# BOARD_POWER.net
KiCad netlist of a schematic drawn in Altium Designer
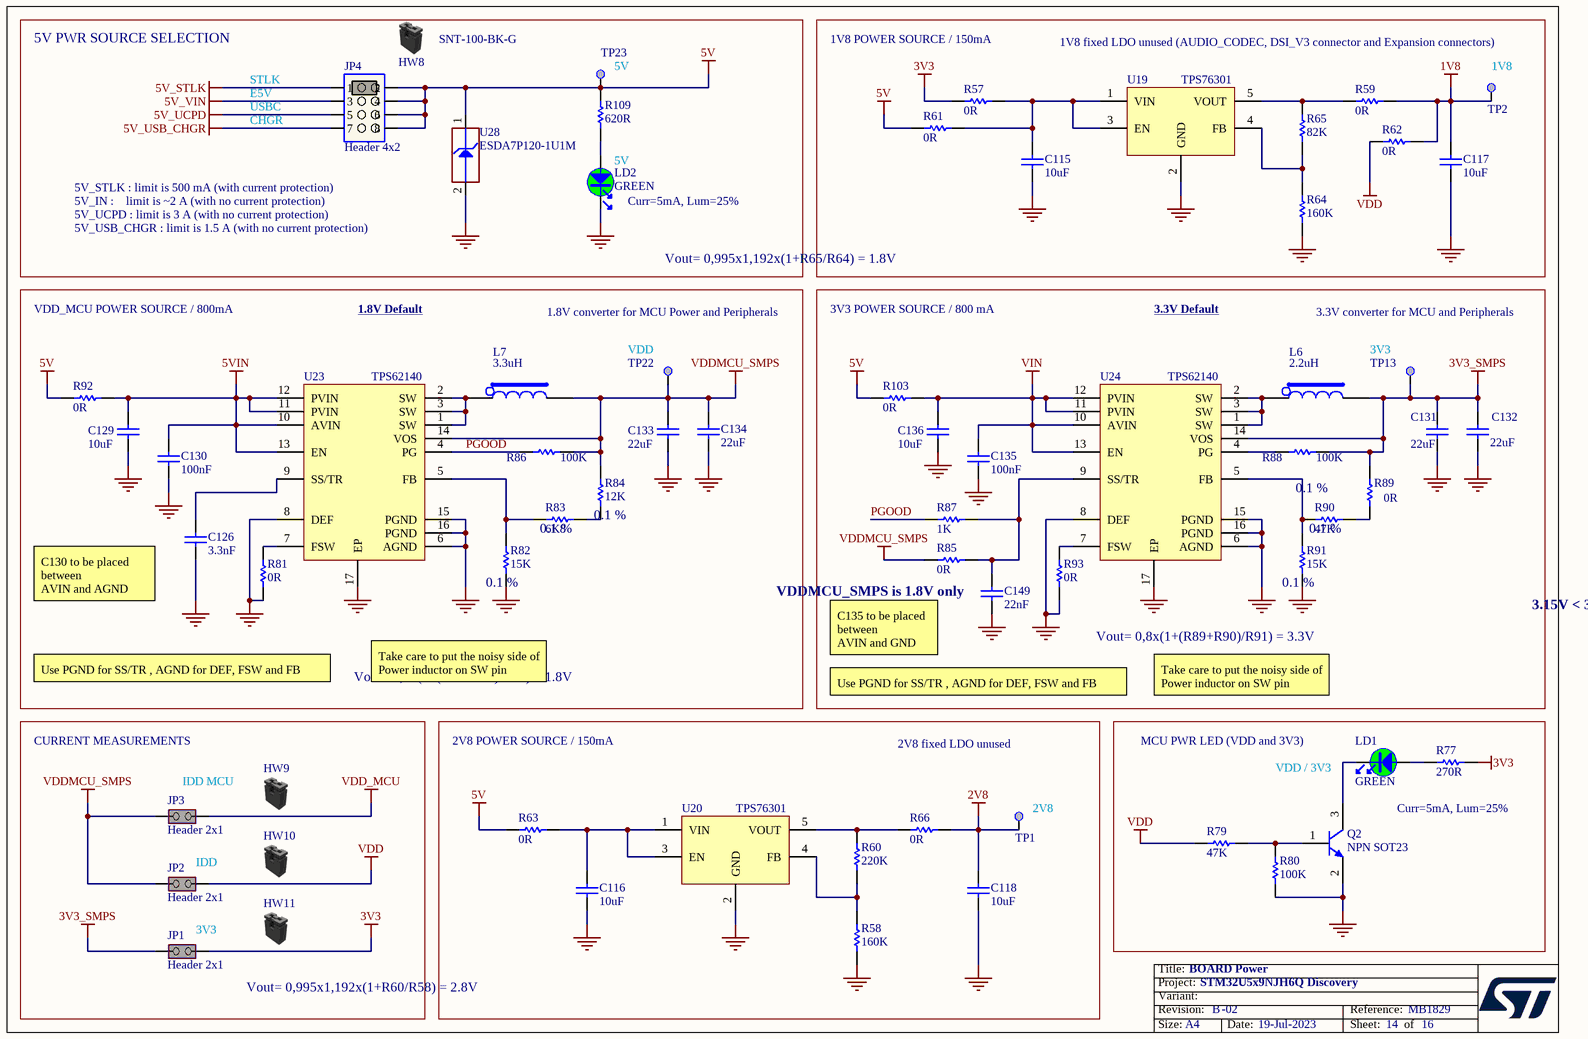
[diagram p0: BOARD_POWER.SchDoc]

(export (version "E")
  (design (tool "Eeschema 10.0.6"))
  (components
    (comp (ref "C115")
      (value "10uF")
      (footprint "MCD_PARTS:C0603_H0P8")
      (description "Capacitor, MLCC, 10uF, 10V, X5R, +/-10%, 0603, T=0.8mm")
      (fields (field (name "INTERNAL_PART_NUMBER") "MCD-02605") (field (name "MANUFACTURER") "YAGEO"))
      (libsource (lib "MCD_PARTS_database") (part "Capacitor"))
    )
    (comp (ref "C116")
      (value "10uF")
      (footprint "MCD_PARTS:C0603_H0P8")
      (description "Capacitor, MLCC, 10uF, 10V, X5R, +/-10%, 0603, T=0.8mm")
      (fields (field (name "INTERNAL_PART_NUMBER") "MCD-02605") (field (name "MANUFACTURER") "YAGEO"))
      (libsource (lib "MCD_PARTS_database") (part "Capacitor"))
    )
    (comp (ref "C117")
      (value "10uF")
      (footprint "MCD_PARTS:C0603_H0P8")
      (description "Capacitor, MLCC, 10uF, 10V, X5R, +/-10%, 0603, T=0.8mm")
      (fields (field (name "INTERNAL_PART_NUMBER") "MCD-02605") (field (name "MANUFACTURER") "YAGEO"))
      (libsource (lib "MCD_PARTS_database") (part "Capacitor"))
    )
    (comp (ref "C118")
      (value "10uF")
      (footprint "MCD_PARTS:C0603_H0P8")
      (description "Capacitor, MLCC, 10uF, 10V, X5R, +/-10%, 0603, T=0.8mm")
      (fields (field (name "INTERNAL_PART_NUMBER") "MCD-02605") (field (name "MANUFACTURER") "YAGEO"))
      (libsource (lib "MCD_PARTS_database") (part "Capacitor"))
    )
    (comp (ref "C126")
      (value "3.3nF")
      (footprint "MCD_PARTS:C0402")
      (description "Capacitor, MLCC, 3.3nF, 50V, X7R, +/-10%, 0402, T=0.5mm")
      (fields (field (name "INTERNAL_PART_NUMBER") "MCD-02628") (field (name "MANUFACTURER") "YAGEO"))
      (libsource (lib "MCD_PARTS_database") (part "Capacitor"))
    )
    (comp (ref "C129")
      (value "10uF")
      (footprint "MCD_PARTS:C1206_H1P6")
      (description "Capacitor, MLCC, 10uF, 25V, X5R, +/-10%, 1206, T=1.6mm")
      (fields (field (name "INTERNAL_PART_NUMBER") "MCD-02610") (field (name "MANUFACTURER") "YAGEO"))
      (libsource (lib "MCD_PARTS_database") (part "Capacitor"))
    )
    (comp (ref "C130")
      (value "100nF")
      (footprint "MCD_PARTS:C0402")
      (description "Capacitor, MLCC, 100nF, 16V, X7R, +/-10%, 0402, T=0.5mm")
      (fields (field (name "INTERNAL_PART_NUMBER") "MCD-00006") (field (name "MANUFACTURER") "YAGEO"))
      (libsource (lib "MCD_PARTS_database") (part "Capacitor"))
    )
    (comp (ref "C131")
      (value "22uF")
      (footprint "MCD_PARTS:C0603_H0P8")
      (description "Capacitor, MLCC, 22uF, 10V, X5R, +/-20%, 0603, T=0.8mm")
      (fields (field (name "INTERNAL_PART_NUMBER") "MCD-02607") (field (name "MANUFACTURER") "YAGEO"))
      (libsource (lib "MCD_PARTS_database") (part "Capacitor"))
    )
    (comp (ref "C132")
      (value "22uF")
      (footprint "MCD_PARTS:C0603_H0P8")
      (description "Capacitor, MLCC, 22uF, 10V, X5R, +/-20%, 0603, T=0.8mm")
      (fields (field (name "INTERNAL_PART_NUMBER") "MCD-02607") (field (name "MANUFACTURER") "YAGEO"))
      (libsource (lib "MCD_PARTS_database") (part "Capacitor"))
    )
    (comp (ref "C133")
      (value "22uF")
      (footprint "MCD_PARTS:C0603_H0P8")
      (description "Capacitor, MLCC, 22uF, 10V, X5R, +/-20%, 0603, T=0.8mm")
      (fields (field (name "INTERNAL_PART_NUMBER") "MCD-02607") (field (name "MANUFACTURER") "YAGEO"))
      (libsource (lib "MCD_PARTS_database") (part "Capacitor"))
    )
    (comp (ref "C134")
      (value "22uF")
      (footprint "MCD_PARTS:C0603_H0P8")
      (description "Capacitor, MLCC, 22uF, 10V, X5R, +/-20%, 0603, T=0.8mm")
      (fields (field (name "INTERNAL_PART_NUMBER") "MCD-02607") (field (name "MANUFACTURER") "YAGEO"))
      (libsource (lib "MCD_PARTS_database") (part "Capacitor"))
    )
    (comp (ref "C135")
      (value "100nF")
      (footprint "MCD_PARTS:C0402")
      (description "Capacitor, MLCC, 100nF, 16V, X7R, +/-10%, 0402, T=0.5mm")
      (fields (field (name "INTERNAL_PART_NUMBER") "MCD-00006") (field (name "MANUFACTURER") "YAGEO"))
      (libsource (lib "MCD_PARTS_database") (part "Capacitor"))
    )
    (comp (ref "C136")
      (value "10uF")
      (footprint "MCD_PARTS:C1206_H1P6")
      (description "Capacitor, MLCC, 10uF, 25V, X5R, +/-10%, 1206, T=1.6mm")
      (fields (field (name "INTERNAL_PART_NUMBER") "MCD-02610") (field (name "MANUFACTURER") "YAGEO"))
      (libsource (lib "MCD_PARTS_database") (part "Capacitor"))
    )
    (comp (ref "C149")
      (value "22nF")
      (footprint "MCD_PARTS:C0402")
      (description "Capacitor, MLCC, 22nF, 50V, X7R, +/-10%, 0402, T=0.5mm")
      (fields (field (name "INTERNAL_PART_NUMBER") "MCD-03051") (field (name "MANUFACTURER") "YAGEO"))
      (libsource (lib "MCD_PARTS_database") (part "Capacitor"))
    )
    (comp (ref "HW8")
      (value "SNT-100-BK-G")
      (description "SHUNT 2.54mm BLACK")
      (fields (field (name "INTERNAL_PART_NUMBER") "MCD-00043") (field (name "MANUFACTURER") "SAMTEC"))
      (libsource (lib "MCD_PARTS_database") (part "Shunt Black 2.54mm"))
    )
    (comp (ref "HW9")
      (value "Shunt Black 2.54mm")
      (description "SHUNT 2.54mm BLACK")
      (fields (field (name "INTERNAL_PART_NUMBER") "MCD-00043") (field (name "MANUFACTURER") "SAMTEC"))
      (libsource (lib "MCD_PARTS_database") (part "Shunt Black 2.54mm"))
    )
    (comp (ref "HW10")
      (value "Shunt Black 2.54mm")
      (description "SHUNT 2.54mm BLACK")
      (fields (field (name "INTERNAL_PART_NUMBER") "MCD-00043") (field (name "MANUFACTURER") "SAMTEC"))
      (libsource (lib "MCD_PARTS_database") (part "Shunt Black 2.54mm"))
    )
    (comp (ref "HW11")
      (value "Shunt Black 2.54mm")
      (description "SHUNT 2.54mm BLACK")
      (fields (field (name "INTERNAL_PART_NUMBER") "MCD-00043") (field (name "MANUFACTURER") "SAMTEC"))
      (libsource (lib "MCD_PARTS_database") (part "Shunt Black 2.54mm"))
    )
    (comp (ref "JP1")
      (value "Header 2x1")
      (footprint "MCD_PARTS:CON_SAMTEC_TSW-102-07-G-S")
      (description "Header, 2x1, 2.54mm, VR, TH, T=5.84mm/2.54mm")
      (fields (field (name "INTERNAL_PART_NUMBER") "MCD-00683") (field (name "MANUFACTURER") "SAMTEC"))
      (libsource (lib "MCD_PARTS_database") (part "Jumper_Header 2x1 Fitted"))
    )
    (comp (ref "JP2")
      (value "Header 2x1")
      (footprint "MCD_PARTS:CON_SAMTEC_TSW-102-07-G-S")
      (description "Header, 2x1, 2.54mm, VR, TH, T=5.84mm/2.54mm")
      (fields (field (name "INTERNAL_PART_NUMBER") "MCD-00683") (field (name "MANUFACTURER") "SAMTEC"))
      (libsource (lib "MCD_PARTS_database") (part "Jumper_Header 2x1 Fitted"))
    )
    (comp (ref "JP3")
      (value "Header 2x1")
      (footprint "MCD_PARTS:CON_SAMTEC_TSW-102-07-G-S")
      (description "Header, 2x1, 2.54mm, VR, TH, T=5.84mm/2.54mm")
      (fields (field (name "INTERNAL_PART_NUMBER") "MCD-00683") (field (name "MANUFACTURER") "SAMTEC"))
      (libsource (lib "MCD_PARTS_database") (part "Jumper_Header 2x1 Fitted"))
    )
    (comp (ref "JP4")
      (value "Header 4x2")
      (footprint "MCD_PARTS:CON_SAMTEC_TSW-104-07-X-D")
      (description "Header, 4x2, 2.54mm, VR, TH, T=5.84mm/2.54mm")
      (fields
        (field (name "INTERNAL_PART_NUMBER") "MCD-00686")
        (field (name "MANUFACTURER_PART_NUMBER") "TSW-104-07-G-D")
      )
      (libsource (lib "MCD_PARTS_database") (part "Jumper_Header 4x2 Fitted 1-2"))
    )
    (comp (ref "L6")
      (value "2.2uH")
      (footprint "MCD_PARTS:IND_COILCRAFT_XGL4020")
      (description "Inductor, 2.2uH, +/-20%, 8.9A, 0R022, 4x4mm, T=2.1mm")
      (fields (field (name "INTERNAL_PART_NUMBER") "MCD-02582") (field (name "MANUFACTURER") "COILCRAFT"))
      (libsource (lib "MCD_PARTS_database") (part "INDUCTOR_POWER_WINDING"))
    )
    (comp (ref "L7")
      (value "3.3uH")
      (footprint "MCD_PARTS:IND_COILCRAFT_XGL4020")
      (description "Inductor, 3.3uH, +/-20%, 6.6A, 0R034, 4x4mm, T=2.1mm")
      (fields (field (name "INTERNAL_PART_NUMBER") "MCD-02581") (field (name "MANUFACTURER") "COILCRAFT"))
      (libsource (lib "MCD_PARTS_database") (part "INDUCTOR_POWER_WINDING"))
    )
    (comp (ref "LD1")
      (value "GREEN")
      (footprint "MCD_PARTS:LED_0603_OSRAM_LG-Q396-PS-35_GREEN_1A2K_H0P4")
      (description "LED Green, 0603 SMD, Forward Voltage Typ=2V, Max=2.5V")
      (fields
        (field (name "INTERNAL_PART_NUMBER") "MCD-00588")
        (field (name "MANUFACTURER") "OSRAM OPTO SEMICONDUCTORS")
      )
      (libsource (lib "MCD_PARTS_database") (part "LED_green"))
    )
    (comp (ref "LD2")
      (value "GREEN")
      (footprint "MCD_PARTS:LED_0603_OSRAM_LG-Q396-PS-35_GREEN_1A2K_H0P4")
      (description "LED Green, 0603 SMD, Forward Voltage Typ=2V, Max=2.5V")
      (fields
        (field (name "INTERNAL_PART_NUMBER") "MCD-00588")
        (field (name "MANUFACTURER") "OSRAM OPTO SEMICONDUCTORS")
      )
      (libsource (lib "MCD_PARTS_database") (part "LED_green"))
    )
    (comp (ref "Q2")
      (value "NPN SOT23")
      (footprint "MCD_PARTS:NPN_SOT23")
      (description "NPN Bipolar Transistor")
      (fields
        (field (name "INTERNAL_PART_NUMBER") "MCD-00073")
        (field (name "MANUFACTURER_PART_NUMBER") "BSR14")
      )
      (libsource (lib "MCD_PARTS_database") (part "9013-SOT23"))
    )
    (comp (ref "R57")
      (value "0R")
      (footprint "MCD_PARTS:R0402")
      (description "Resistor, 0R, 0402, +/-5%, 1/16W")
      (fields (field (name "INTERNAL_PART_NUMBER") "MCD-00052") (field (name "MANUFACTURER") "YAGEO"))
      (libsource (lib "MCD_PARTS_database") (part "Resistor"))
    )
    (comp (ref "R58")
      (value "160K")
      (footprint "MCD_PARTS:R0402")
      (description "Resistor, 160K, 0402, +/-1%, 1/16W")
      (fields (field (name "INTERNAL_PART_NUMBER") "MCD-00405") (field (name "MANUFACTURER") "YAGEO"))
      (libsource (lib "MCD_PARTS_database") (part "Resistor"))
    )
    (comp (ref "R59")
      (value "0R")
      (footprint "MCD_PARTS:R0603")
      (description "Resistor, 0R, 0603, +/- 0.5mR, 1/4W")
      (fields (field (name "INTERNAL_PART_NUMBER") "MCD-00181") (field (name "MANUFACTURER") "ROHM"))
      (libsource (lib "MCD_PARTS_database") (part "Resistor"))
    )
    (comp (ref "R60")
      (value "220K")
      (footprint "MCD_PARTS:R0402")
      (description "Resistor, 220K, 0402, +/-1%, 1/16W")
      (fields (field (name "INTERNAL_PART_NUMBER") "MCD-00164") (field (name "MANUFACTURER") "YAGEO"))
      (libsource (lib "MCD_PARTS_database") (part "Resistor"))
    )
    (comp (ref "R61")
      (value "0R")
      (footprint "MCD_PARTS:R0402")
      (description "Resistor, 0R, 0402, +/-5%, 1/16W")
      (fields (field (name "INTERNAL_PART_NUMBER") "MCD-00052") (field (name "MANUFACTURER") "YAGEO"))
      (libsource (lib "MCD_PARTS_database") (part "Resistor"))
    )
    (comp (ref "R62")
      (value "0R")
      (footprint "MCD_PARTS:R0603")
      (description "Resistor, 0R, 0603, +/- 0.5mR, 1/4W")
      (fields (field (name "INTERNAL_PART_NUMBER") "MCD-00181") (field (name "MANUFACTURER") "ROHM"))
      (libsource (lib "MCD_PARTS_database") (part "Resistor"))
    )
    (comp (ref "R63")
      (value "0R")
      (footprint "MCD_PARTS:R0402")
      (description "Resistor, 0R, 0402, +/-5%, 1/16W")
      (fields (field (name "INTERNAL_PART_NUMBER") "MCD-00052") (field (name "MANUFACTURER") "YAGEO"))
      (libsource (lib "MCD_PARTS_database") (part "Resistor"))
    )
    (comp (ref "R64")
      (value "160K")
      (footprint "MCD_PARTS:R0402")
      (description "Resistor, 160K, 0402, +/-1%, 1/16W")
      (fields (field (name "INTERNAL_PART_NUMBER") "MCD-00405") (field (name "MANUFACTURER") "YAGEO"))
      (libsource (lib "MCD_PARTS_database") (part "Resistor"))
    )
    (comp (ref "R65")
      (value "82K")
      (footprint "MCD_PARTS:R0402")
      (description "Resistor, 82K, 0402, +/-1%, 1/16W")
      (fields (field (name "INTERNAL_PART_NUMBER") "MCD-00531") (field (name "MANUFACTURER") "YAGEO"))
      (libsource (lib "MCD_PARTS_database") (part "Resistor"))
    )
    (comp (ref "R66")
      (value "0R")
      (footprint "MCD_PARTS:R0603")
      (description "Resistor, 0R, 0603, +/- 0.5mR, 1/4W")
      (fields (field (name "INTERNAL_PART_NUMBER") "MCD-00181") (field (name "MANUFACTURER") "ROHM"))
      (libsource (lib "MCD_PARTS_database") (part "Resistor"))
    )
    (comp (ref "R77")
      (value "270R")
      (footprint "MCD_PARTS:R0402")
      (description "Resistor, 270R, 0402, +/-1%, 1/16W")
      (fields (field (name "INTERNAL_PART_NUMBER") "MCD-00441") (field (name "MANUFACTURER") "YAGEO"))
      (libsource (lib "MCD_PARTS_database") (part "Resistor"))
    )
    (comp (ref "R79")
      (value "47K")
      (footprint "MCD_PARTS:R0603")
      (description "Resistor, 47K, 0603, 1%, 1/10W")
      (fields
        (field (name "INTERNAL_PART_NUMBER") "MCD-00222")
        (field (name "MANUFACTURER_PART_NUMBER") "RC0603FR-0747KL")
      )
      (libsource (lib "MCD_PARTS_database") (part "Resistor"))
    )
    (comp (ref "R80")
      (value "100K")
      (footprint "MCD_PARTS:R0603")
      (description "Resistor, 100K, 0603, +/- 1%, 1/10W")
      (fields
        (field (name "INTERNAL_PART_NUMBER") "MCD-00223")
        (field (name "MANUFACTURER_PART_NUMBER") "RC0603FR-07100KL")
      )
      (libsource (lib "MCD_PARTS_database") (part "Resistor"))
    )
    (comp (ref "R81")
      (value "0R")
      (footprint "MCD_PARTS:R0402")
      (description "Resistor, 0R, 0402, +/-5%, 1/16W")
      (fields (field (name "INTERNAL_PART_NUMBER") "MCD-00052") (field (name "MANUFACTURER") "YAGEO"))
      (libsource (lib "MCD_PARTS_database") (part "Resistor"))
    )
    (comp (ref "R82")
      (value "15K")
      (footprint "MCD_PARTS:R0402")
      (description "Resistor, 15K, 0402, +/-0.1%, 1/16W, +/-25ppm/°C")
      (fields (field (name "INTERNAL_PART_NUMBER") "MCD-02570") (field (name "MANUFACTURER") "YAGEO"))
      (libsource (lib "MCD_PARTS_database") (part "Resistor"))
    )
    (comp (ref "R83")
      (value "6K8")
      (footprint "MCD_PARTS:R0402")
      (description "Resistor, 6K8, 0402, +/-0.1%, 1/16W, +/-25ppm/°C")
      (fields (field (name "INTERNAL_PART_NUMBER") "MCD-02568") (field (name "MANUFACTURER") "YAGEO"))
      (libsource (lib "MCD_PARTS_database") (part "Resistor"))
    )
    (comp (ref "R84")
      (value "12K")
      (footprint "MCD_PARTS:R0402")
      (description "Resistor, 12K, 0402, +/-0.1%, 1/16W, +/-25ppm/°C")
      (fields (field (name "INTERNAL_PART_NUMBER") "MCD-02567") (field (name "MANUFACTURER") "YAGEO"))
      (libsource (lib "MCD_PARTS_database") (part "Resistor"))
    )
    (comp (ref "R85")
      (value "0R")
      (footprint "MCD_PARTS:R0402")
      (description "Resistor, 0R, 0402, +/-5%, 1/16W")
      (fields (field (name "INTERNAL_PART_NUMBER") "MCD-00052") (field (name "MANUFACTURER") "YAGEO"))
      (libsource (lib "MCD_PARTS_database") (part "Resistor"))
    )
    (comp (ref "R86")
      (value "100K")
      (footprint "MCD_PARTS:R0402")
      (description "Resistor, 100K, 0402, +/-1%, 1/16W")
      (fields (field (name "INTERNAL_PART_NUMBER") "MCD-00059") (field (name "MANUFACTURER") "YAGEO"))
      (libsource (lib "MCD_PARTS_database") (part "Resistor"))
    )
    (comp (ref "R87")
      (value "1K")
      (footprint "MCD_PARTS:R0402")
      (description "Resistor, 1K, 0402, +/-1%,1/16W")
      (fields (field (name "INTERNAL_PART_NUMBER") "MCD-00061") (field (name "MANUFACTURER") "YAGEO"))
      (libsource (lib "MCD_PARTS_database") (part "Resistor"))
    )
    (comp (ref "R88")
      (value "100K")
      (footprint "MCD_PARTS:R0402")
      (description "Resistor, 100K, 0402, +/-1%, 1/16W")
      (fields (field (name "INTERNAL_PART_NUMBER") "MCD-00059") (field (name "MANUFACTURER") "YAGEO"))
      (libsource (lib "MCD_PARTS_database") (part "Resistor"))
    )
    (comp (ref "R89")
      (value "0R")
      (footprint "MCD_PARTS:R0402")
      (description "Resistor, 0R, 0402, +/-5%, 1/16W")
      (fields (field (name "INTERNAL_PART_NUMBER") "MCD-00052") (field (name "MANUFACTURER") "YAGEO"))
      (libsource (lib "MCD_PARTS_database") (part "Resistor"))
    )
    (comp (ref "R90")
      (value "47K")
      (footprint "MCD_PARTS:R0402")
      (description "Resistor, 47K, 0402, +/-0.1%, 1/16W, +/-25ppm/°C")
      (fields (field (name "INTERNAL_PART_NUMBER") "MCD-02550") (field (name "MANUFACTURER") "YAGEO"))
      (libsource (lib "MCD_PARTS_database") (part "Resistor"))
    )
    (comp (ref "R91")
      (value "15K")
      (footprint "MCD_PARTS:R0402")
      (description "Resistor, 15K, 0402, +/-0.1%, 1/16W, +/-25ppm/°C")
      (fields (field (name "INTERNAL_PART_NUMBER") "MCD-02570") (field (name "MANUFACTURER") "YAGEO"))
      (libsource (lib "MCD_PARTS_database") (part "Resistor"))
    )
    (comp (ref "R92")
      (value "0R")
      (footprint "MCD_PARTS:R0603")
      (description "Resistor, 0R, 0603, +/- 0.5mR, 1/4W")
      (fields (field (name "INTERNAL_PART_NUMBER") "MCD-00181") (field (name "MANUFACTURER") "ROHM"))
      (libsource (lib "MCD_PARTS_database") (part "Resistor"))
    )
    (comp (ref "R93")
      (value "0R")
      (footprint "MCD_PARTS:R0402")
      (description "Resistor, 0R, 0402, +/-5%, 1/16W")
      (fields (field (name "INTERNAL_PART_NUMBER") "MCD-00052") (field (name "MANUFACTURER") "YAGEO"))
      (libsource (lib "MCD_PARTS_database") (part "Resistor"))
    )
    (comp (ref "R103")
      (value "0R")
      (footprint "MCD_PARTS:R0603")
      (description "Resistor, 0R, 0603, +/- 0.5mR, 1/4W")
      (fields (field (name "INTERNAL_PART_NUMBER") "MCD-00181") (field (name "MANUFACTURER") "ROHM"))
      (libsource (lib "MCD_PARTS_database") (part "Resistor"))
    )
    (comp (ref "R109")
      (value "620R")
      (footprint "MCD_PARTS:R0402")
      (description "Resistor, 620R, 0402, +/-1%, 1/16W")
      (fields (field (name "INTERNAL_PART_NUMBER") "MCD-00499") (field (name "MANUFACTURER") "YAGEO"))
      (libsource (lib "MCD_PARTS_database") (part "Resistor"))
    )
    (comp (ref "TP1")
      (value "Test Point")
      (footprint "MCD_PARTS:TP_SMD_1MM")
      (description "Test Point 1mm")
      (fields (field (name "INTERNAL_PART_NUMBER") "MCD-00074"))
      (libsource (lib "MCD_PARTS_database") (part "Test Point"))
    )
    (comp (ref "TP2")
      (value "Test Point")
      (footprint "MCD_PARTS:TP_SMD_1MM")
      (description "Test Point 1mm")
      (fields (field (name "INTERNAL_PART_NUMBER") "MCD-00074"))
      (libsource (lib "MCD_PARTS_database") (part "Test Point"))
    )
    (comp (ref "TP13")
      (value "Test Point")
      (footprint "MCD_PARTS:TP_SMD_1MM")
      (description "Test Point 1mm")
      (fields (field (name "INTERNAL_PART_NUMBER") "MCD-00074"))
      (libsource (lib "MCD_PARTS_database") (part "Test Point"))
    )
    (comp (ref "TP22")
      (value "Test Point")
      (footprint "MCD_PARTS:TP_SMD_1MM")
      (description "Test Point 1mm")
      (fields (field (name "INTERNAL_PART_NUMBER") "MCD-00074"))
      (libsource (lib "MCD_PARTS_database") (part "Test Point"))
    )
    (comp (ref "TP23")
      (value "Test Point")
      (footprint "MCD_PARTS:TP_SMD_1MM")
      (description "Test Point 1mm")
      (fields (field (name "INTERNAL_PART_NUMBER") "MCD-00074"))
      (libsource (lib "MCD_PARTS_database") (part "Test Point"))
    )
    (comp (ref "U19")
      (value "TPS76301")
      (footprint "MCD_PARTS:ICC_SOT23-5L_H1P45")
      (description "LDO VOLTAGE REGULATOR, Adjustable, 150mA,")
      (fields
        (field (name "INTERNAL_PART_NUMBER") "MCD-02175")
        (field (name "MANUFACTURER_PART_NUMBER") "TPS76301DBVT")
      )
      (libsource (lib "MCD_PARTS_database") (part "TPS76301"))
    )
    (comp (ref "U20")
      (value "TPS76301")
      (footprint "MCD_PARTS:ICC_SOT23-5L_H1P45")
      (description "LDO VOLTAGE REGULATOR, Adjustable, 150mA,")
      (fields
        (field (name "INTERNAL_PART_NUMBER") "MCD-02175")
        (field (name "MANUFACTURER_PART_NUMBER") "TPS76301DBVT")
      )
      (libsource (lib "MCD_PARTS_database") (part "TPS76301"))
    )
    (comp (ref "U23")
      (value "TPS62140")
      (footprint "MCD_PARTS:ICC_VQFN16-EPAD_3X3_P050")
      (description "Buck converter, 2A, 3V to 17V input, Fsw 1.25/2.5 MHz, 3x3 VQFN16")
      (fields
        (field (name "INTERNAL_PART_NUMBER") "MCD-02580")
        (field (name "MANUFACTURER") "TEXAS INSTRUMENTS")
      )
      (libsource (lib "MCD_PARTS_database") (part "TPS62140RGTR"))
    )
    (comp (ref "U24")
      (value "TPS62140")
      (footprint "MCD_PARTS:ICC_VQFN16-EPAD_3X3_P050")
      (description "Buck converter, 2A, 3V to 17V input, Fsw 1.25/2.5 MHz, 3x3 VQFN16")
      (fields
        (field (name "INTERNAL_PART_NUMBER") "MCD-02580")
        (field (name "MANUFACTURER") "TEXAS INSTRUMENTS")
      )
      (libsource (lib "MCD_PARTS_database") (part "TPS62140RGTR"))
    )
    (comp (ref "U28")
      (value "ESDA7P120-1U1M")
      (footprint "MCD_PARTS:ESD_QFN1610_2N_1K_2A")
      (description "High power transient voltage suppressor")
      (fields
        (field (name "INTERNAL_PART_NUMBER") "MCD-01026")
        (field (name "MANUFACTURER") "STMICROELECTRONICS")
      )
      (libsource (lib "MCD_PARTS_database") (part "ESD-TRANSIL"))
    )
  )
  (nets
    (net (code "1") (name "/PGOOD") (class "Default")
      (node (ref "R86") (pin "1") (pinfunction "1_1") (pintype "passive"))
      (node (ref "R87") (pin "2") (pinfunction "2_2") (pintype "passive"))
      (node (ref "U23") (pin "4") (pinfunction "PG_4") (pintype "passive"))
    )
    (net (code "2") (name "1V8") (class "Default")
      (node (ref "C117") (pin "2") (pinfunction "2_2") (pintype "passive"))
      (node (ref "R59") (pin "2") (pinfunction "2_2") (pintype "passive"))
      (node (ref "R62") (pin "2") (pinfunction "2_2") (pintype "passive"))
      (node (ref "TP2") (pin "1") (pinfunction "1_1") (pintype "passive"))
    )
    (net (code "3") (name "2V8") (class "Default")
      (node (ref "C118") (pin "2") (pinfunction "2_2") (pintype "passive"))
      (node (ref "R66") (pin "2") (pinfunction "2_2") (pintype "passive"))
      (node (ref "TP1") (pin "1") (pinfunction "1_1") (pintype "passive"))
    )
    (net (code "4") (name "3V3") (class "Default")
      (node (ref "JP1") (pin "2") (pinfunction "NO_2") (pintype "passive"))
      (node (ref "R57") (pin "1") (pinfunction "1_1") (pintype "passive"))
      (node (ref "R77") (pin "2") (pinfunction "2_2") (pintype "passive"))
    )
    (net (code "5") (name "3V3_SMPS") (class "Default")
      (node (ref "C131") (pin "1") (pinfunction "1_1") (pintype "passive"))
      (node (ref "C132") (pin "2") (pinfunction "2_2") (pintype "passive"))
      (node (ref "JP1") (pin "1") (pinfunction "COMMON_1") (pintype "passive"))
      (node (ref "L6") (pin "2") (pinfunction "2_2") (pintype "passive"))
      (node (ref "R88") (pin "2") (pinfunction "2_2") (pintype "passive"))
      (node (ref "R89") (pin "2") (pinfunction "2_2") (pintype "passive"))
      (node (ref "TP13") (pin "1") (pinfunction "1_1") (pintype "passive"))
      (node (ref "U24") (pin "14") (pinfunction "VOS_14") (pintype "passive"))
    )
    (net (code "6") (name "5V") (class "Default")
      (node (ref "JP4") (pin "2") (pinfunction "2_2") (pintype "passive"))
      (node (ref "JP4") (pin "4") (pinfunction "4_4") (pintype "passive"))
      (node (ref "JP4") (pin "6") (pinfunction "6_6") (pintype "passive"))
      (node (ref "JP4") (pin "8") (pinfunction "8_8") (pintype "passive"))
      (node (ref "R103") (pin "1") (pinfunction "1_1") (pintype "passive"))
      (node (ref "R109") (pin "2") (pinfunction "2_2") (pintype "passive"))
      (node (ref "R61") (pin "1") (pinfunction "1_1") (pintype "passive"))
      (node (ref "R63") (pin "1") (pinfunction "1_1") (pintype "passive"))
      (node (ref "R92") (pin "1") (pinfunction "1_1") (pintype "passive"))
      (node (ref "TP23") (pin "1") (pinfunction "1_1") (pintype "passive"))
      (node (ref "U28") (pin "1") (pinfunction "IO1_1") (pintype "passive"))
    )
    (net (code "7") (name "5VIN") (class "Default")
      (node (ref "C129") (pin "2") (pinfunction "2_2") (pintype "passive"))
      (node (ref "C130") (pin "2") (pinfunction "2_2") (pintype "passive"))
      (node (ref "R92") (pin "2") (pinfunction "2_2") (pintype "passive"))
      (node (ref "U23") (pin "10") (pinfunction "AVIN_10") (pintype "passive"))
      (node (ref "U23") (pin "11") (pinfunction "PVIN_11") (pintype "passive"))
      (node (ref "U23") (pin "12") (pinfunction "PVIN_12") (pintype "passive"))
      (node (ref "U23") (pin "13") (pinfunction "EN_13") (pintype "passive"))
    )
    (net (code "8") (name "5V_STLK") (class "Default")
      (node (ref "JP4") (pin "1") (pinfunction "1_1") (pintype "passive"))
    )
    (net (code "9") (name "5V_UCPD") (class "Default")
      (node (ref "JP4") (pin "5") (pinfunction "5_5") (pintype "passive"))
    )
    (net (code "10") (name "5V_USB_CHGR") (class "Default")
      (node (ref "JP4") (pin "7") (pinfunction "7_7") (pintype "passive"))
    )
    (net (code "11") (name "5V_VIN") (class "Default")
      (node (ref "JP4") (pin "3") (pinfunction "3_3") (pintype "passive"))
    )
    (net (code "12") (name "GND") (class "Default")
      (node (ref "C115") (pin "1") (pinfunction "1_1") (pintype "passive"))
      (node (ref "C116") (pin "1") (pinfunction "1_1") (pintype "passive"))
      (node (ref "C117") (pin "1") (pinfunction "1_1") (pintype "passive"))
      (node (ref "C118") (pin "1") (pinfunction "1_1") (pintype "passive"))
      (node (ref "C126") (pin "1") (pinfunction "1_1") (pintype "passive"))
      (node (ref "C129") (pin "1") (pinfunction "1_1") (pintype "passive"))
      (node (ref "C130") (pin "1") (pinfunction "1_1") (pintype "passive"))
      (node (ref "C131") (pin "2") (pinfunction "2_2") (pintype "passive"))
      (node (ref "C132") (pin "1") (pinfunction "1_1") (pintype "passive"))
      (node (ref "C133") (pin "1") (pinfunction "1_1") (pintype "passive"))
      (node (ref "C134") (pin "1") (pinfunction "1_1") (pintype "passive"))
      (node (ref "C135") (pin "1") (pinfunction "1_1") (pintype "passive"))
      (node (ref "C136") (pin "1") (pinfunction "1_1") (pintype "passive"))
      (node (ref "C149") (pin "1") (pinfunction "1_1") (pintype "passive"))
      (node (ref "LD2") (pin "2") (pintype "passive"))
      (node (ref "Q2") (pin "2") (pinfunction "E_2") (pintype "passive"))
      (node (ref "R58") (pin "1") (pinfunction "1_1") (pintype "passive"))
      (node (ref "R64") (pin "1") (pinfunction "1_1") (pintype "passive"))
      (node (ref "R80") (pin "1") (pinfunction "1_1") (pintype "passive"))
      (node (ref "R81") (pin "1") (pinfunction "1_1") (pintype "passive"))
      (node (ref "R82") (pin "1") (pinfunction "1_1") (pintype "passive"))
      (node (ref "R91") (pin "1") (pinfunction "1_1") (pintype "passive"))
      (node (ref "R93") (pin "1") (pinfunction "1_1") (pintype "passive"))
      (node (ref "U19") (pin "2") (pinfunction "GND_2") (pintype "passive"))
      (node (ref "U20") (pin "2") (pinfunction "GND_2") (pintype "passive"))
      (node (ref "U23") (pin "15") (pinfunction "PGND_15") (pintype "passive"))
      (node (ref "U23") (pin "16") (pinfunction "PGND_16") (pintype "passive"))
      (node (ref "U23") (pin "17") (pinfunction "EP_17") (pintype "passive"))
      (node (ref "U23") (pin "6") (pinfunction "AGND_6") (pintype "passive"))
      (node (ref "U23") (pin "8") (pinfunction "DEF_8") (pintype "passive"))
      (node (ref "U24") (pin "15") (pinfunction "PGND_15") (pintype "passive"))
      (node (ref "U24") (pin "16") (pinfunction "PGND_16") (pintype "passive"))
      (node (ref "U24") (pin "17") (pinfunction "EP_17") (pintype "passive"))
      (node (ref "U24") (pin "6") (pinfunction "AGND_6") (pintype "passive"))
      (node (ref "U24") (pin "8") (pinfunction "DEF_8") (pintype "passive"))
      (node (ref "U28") (pin "2") (pinfunction "GND_2") (pintype "passive"))
    )
    (net (code "13") (name "Net-(L6-Pad1)") (class "Default")
      (node (ref "L6") (pin "1") (pinfunction "1_1") (pintype "passive"))
      (node (ref "U24") (pin "1") (pinfunction "SW_1") (pintype "passive"))
      (node (ref "U24") (pin "2") (pinfunction "SW_2") (pintype "passive"))
      (node (ref "U24") (pin "3") (pinfunction "SW_3") (pintype "passive"))
    )
    (net (code "14") (name "Net-(L7-Pad1)") (class "Default")
      (node (ref "L7") (pin "1") (pinfunction "1_1") (pintype "passive"))
      (node (ref "U23") (pin "1") (pinfunction "SW_1") (pintype "passive"))
      (node (ref "U23") (pin "2") (pinfunction "SW_2") (pintype "passive"))
      (node (ref "U23") (pin "3") (pinfunction "SW_3") (pintype "passive"))
    )
    (net (code "15") (name "Net-(LD1-Pad1)") (class "Default")
      (node (ref "LD1") (pin "1") (pintype "passive"))
      (node (ref "R77") (pin "1") (pinfunction "1_1") (pintype "passive"))
    )
    (net (code "16") (name "Net-(LD2-Pad1)") (class "Default")
      (node (ref "LD2") (pin "1") (pintype "passive"))
      (node (ref "R109") (pin "1") (pinfunction "1_1") (pintype "passive"))
    )
    (net (code "17") (name "Net-(Q2-B)") (class "Default")
      (node (ref "Q2") (pin "1") (pinfunction "B_1") (pintype "passive"))
      (node (ref "R79") (pin "2") (pinfunction "2_2") (pintype "passive"))
      (node (ref "R80") (pin "2") (pinfunction "2_2") (pintype "passive"))
    )
    (net (code "18") (name "Net-(Q2-C)") (class "Default")
      (node (ref "LD1") (pin "2") (pintype "passive"))
      (node (ref "Q2") (pin "3") (pinfunction "C_3") (pintype "passive"))
    )
    (net (code "19") (name "Net-(R83-Pad2)") (class "Default")
      (node (ref "R83") (pin "2") (pinfunction "2_2") (pintype "passive"))
      (node (ref "R84") (pin "2") (pinfunction "2_2") (pintype "passive"))
    )
    (net (code "20") (name "Net-(R89-Pad1)") (class "Default")
      (node (ref "R89") (pin "1") (pinfunction "1_1") (pintype "passive"))
      (node (ref "R90") (pin "2") (pinfunction "2_2") (pintype "passive"))
    )
    (net (code "21") (name "Net-(U19-EN)") (class "Default")
      (node (ref "C115") (pin "2") (pinfunction "2_2") (pintype "passive"))
      (node (ref "R57") (pin "2") (pinfunction "2_2") (pintype "passive"))
      (node (ref "R61") (pin "2") (pinfunction "2_2") (pintype "passive"))
      (node (ref "U19") (pin "1") (pinfunction "VIN_1") (pintype "passive"))
      (node (ref "U19") (pin "3") (pinfunction "EN_3") (pintype "passive"))
    )
    (net (code "22") (name "Net-(U19-FB)") (class "Default")
      (node (ref "R64") (pin "2") (pinfunction "2_2") (pintype "passive"))
      (node (ref "R65") (pin "1") (pinfunction "1_1") (pintype "passive"))
      (node (ref "U19") (pin "4") (pinfunction "FB_4") (pintype "passive"))
    )
    (net (code "23") (name "Net-(U19-VOUT)") (class "Default")
      (node (ref "R59") (pin "1") (pinfunction "1_1") (pintype "passive"))
      (node (ref "R65") (pin "2") (pinfunction "2_2") (pintype "passive"))
      (node (ref "U19") (pin "5") (pinfunction "VOUT_5") (pintype "passive"))
    )
    (net (code "24") (name "Net-(U20-EN)") (class "Default")
      (node (ref "C116") (pin "2") (pinfunction "2_2") (pintype "passive"))
      (node (ref "R63") (pin "2") (pinfunction "2_2") (pintype "passive"))
      (node (ref "U20") (pin "1") (pinfunction "VIN_1") (pintype "passive"))
      (node (ref "U20") (pin "3") (pinfunction "EN_3") (pintype "passive"))
    )
    (net (code "25") (name "Net-(U20-FB)") (class "Default")
      (node (ref "R58") (pin "2") (pinfunction "2_2") (pintype "passive"))
      (node (ref "R60") (pin "1") (pinfunction "1_1") (pintype "passive"))
      (node (ref "U20") (pin "4") (pinfunction "FB_4") (pintype "passive"))
    )
    (net (code "26") (name "Net-(U20-VOUT)") (class "Default")
      (node (ref "R60") (pin "2") (pinfunction "2_2") (pintype "passive"))
      (node (ref "R66") (pin "1") (pinfunction "1_1") (pintype "passive"))
      (node (ref "U20") (pin "5") (pinfunction "VOUT_5") (pintype "passive"))
    )
    (net (code "27") (name "Net-(U23-FB)") (class "Default")
      (node (ref "R82") (pin "2") (pinfunction "2_2") (pintype "passive"))
      (node (ref "R83") (pin "1") (pinfunction "1_1") (pintype "passive"))
      (node (ref "U23") (pin "5") (pinfunction "FB_5") (pintype "passive"))
    )
    (net (code "28") (name "Net-(U23-FSW)") (class "Default")
      (node (ref "R81") (pin "2") (pinfunction "2_2") (pintype "passive"))
      (node (ref "U23") (pin "7") (pinfunction "FSW_7") (pintype "passive"))
    )
    (net (code "29") (name "Net-(U23-SS{slash}TR)") (class "Default")
      (node (ref "C126") (pin "2") (pinfunction "2_2") (pintype "passive"))
      (node (ref "U23") (pin "9") (pinfunction "SS/TR_9") (pintype "passive"))
    )
    (net (code "30") (name "Net-(U24-FB)") (class "Default")
      (node (ref "R90") (pin "1") (pinfunction "1_1") (pintype "passive"))
      (node (ref "R91") (pin "2") (pinfunction "2_2") (pintype "passive"))
      (node (ref "U24") (pin "5") (pinfunction "FB_5") (pintype "passive"))
    )
    (net (code "31") (name "Net-(U24-FSW)") (class "Default")
      (node (ref "R93") (pin "2") (pinfunction "2_2") (pintype "passive"))
      (node (ref "U24") (pin "7") (pinfunction "FSW_7") (pintype "passive"))
    )
    (net (code "32") (name "Net-(U24-PG)") (class "Default")
      (node (ref "R88") (pin "1") (pinfunction "1_1") (pintype "passive"))
      (node (ref "U24") (pin "4") (pinfunction "PG_4") (pintype "passive"))
    )
    (net (code "33") (name "Net-(U24-SS{slash}TR)") (class "Default")
      (node (ref "C149") (pin "2") (pinfunction "2_2") (pintype "passive"))
      (node (ref "R85") (pin "1") (pinfunction "1_1") (pintype "passive"))
      (node (ref "R87") (pin "1") (pinfunction "1_1") (pintype "passive"))
      (node (ref "U24") (pin "9") (pinfunction "SS/TR_9") (pintype "passive"))
    )
    (net (code "34") (name "VDD") (class "Default")
      (node (ref "JP2") (pin "2") (pinfunction "NO_2") (pintype "passive"))
      (node (ref "R62") (pin "1") (pinfunction "1_1") (pintype "passive"))
      (node (ref "R79") (pin "1") (pinfunction "1_1") (pintype "passive"))
    )
    (net (code "35") (name "VDDMCU_SMPS") (class "Default")
      (node (ref "C133") (pin "2") (pinfunction "2_2") (pintype "passive"))
      (node (ref "C134") (pin "2") (pinfunction "2_2") (pintype "passive"))
      (node (ref "JP2") (pin "1") (pinfunction "COMMON_1") (pintype "passive"))
      (node (ref "JP3") (pin "1") (pinfunction "COMMON_1") (pintype "passive"))
      (node (ref "L7") (pin "2") (pinfunction "2_2") (pintype "passive"))
      (node (ref "R84") (pin "1") (pinfunction "1_1") (pintype "passive"))
      (node (ref "R85") (pin "2") (pinfunction "2_2") (pintype "passive"))
      (node (ref "R86") (pin "2") (pinfunction "2_2") (pintype "passive"))
      (node (ref "TP22") (pin "1") (pinfunction "1_1") (pintype "passive"))
      (node (ref "U23") (pin "14") (pinfunction "VOS_14") (pintype "passive"))
    )
    (net (code "36") (name "VDD_MCU") (class "Default")
      (node (ref "JP3") (pin "2") (pinfunction "NO_2") (pintype "passive"))
    )
    (net (code "37") (name "VIN") (class "Default")
      (node (ref "C135") (pin "2") (pinfunction "2_2") (pintype "passive"))
      (node (ref "C136") (pin "2") (pinfunction "2_2") (pintype "passive"))
      (node (ref "R103") (pin "2") (pinfunction "2_2") (pintype "passive"))
      (node (ref "U24") (pin "10") (pinfunction "AVIN_10") (pintype "passive"))
      (node (ref "U24") (pin "11") (pinfunction "PVIN_11") (pintype "passive"))
      (node (ref "U24") (pin "12") (pinfunction "PVIN_12") (pintype "passive"))
      (node (ref "U24") (pin "13") (pinfunction "EN_13") (pintype "passive"))
    )
  )
)
